# neural_network.net
KiCad netlist of a schematic drawn in EAGLE
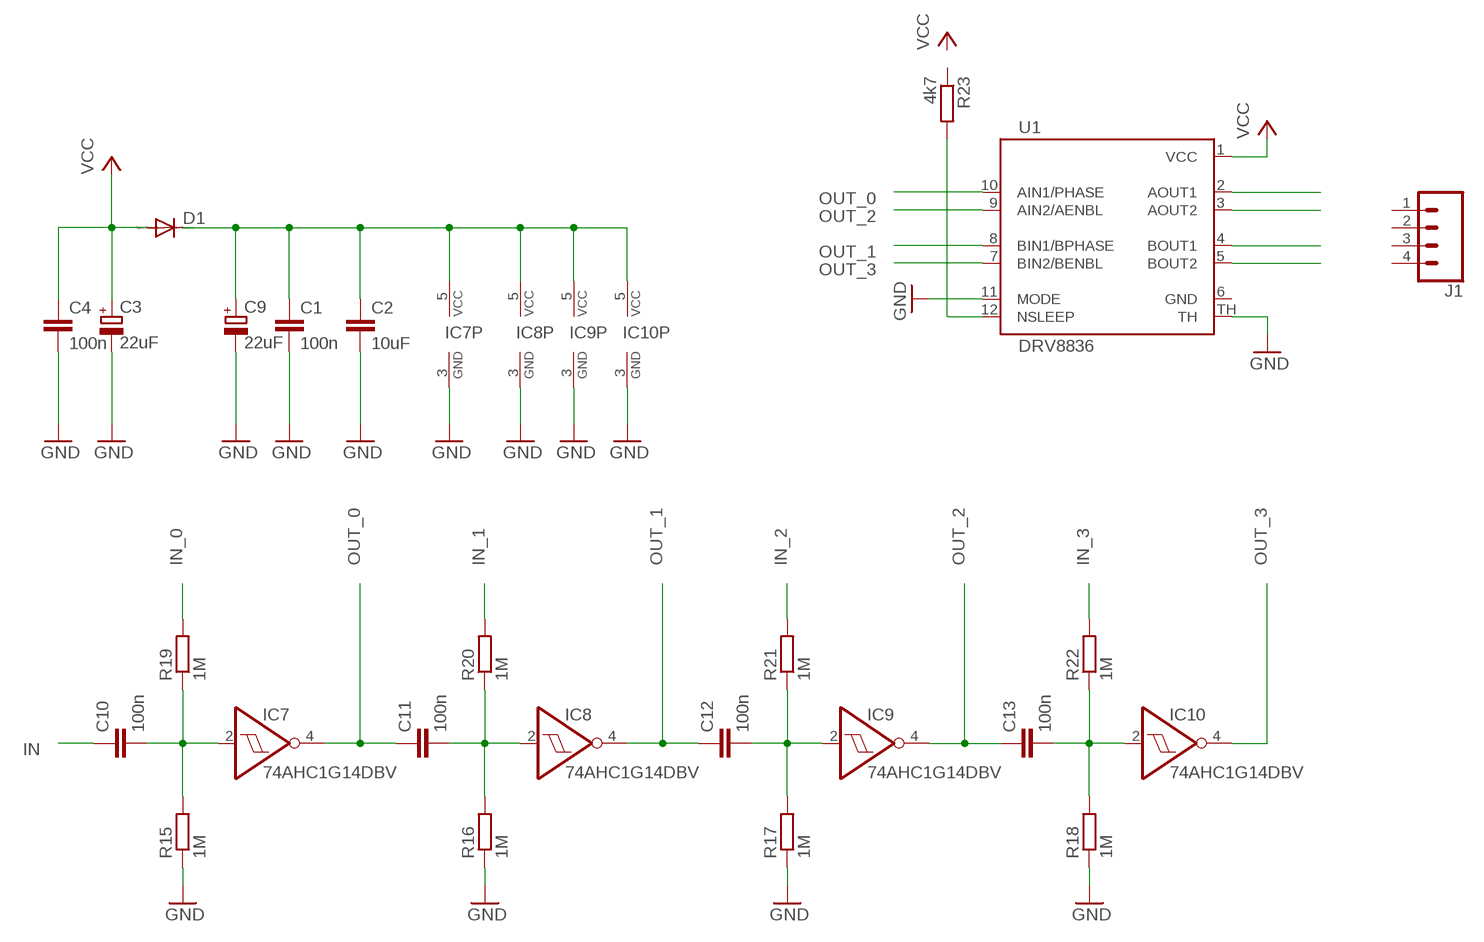
[diagram p0: schematic, sheet 1]

(export (version "E")
  (design (tool "Eeschema 10.0.6"))
  (components
    (comp (ref "C1")
      (value "100n")
      (footprint "eagle-import:C0805")
      (libsource (lib "eagle-import") (part "C-EUC0805"))
    )
    (comp (ref "C2")
      (value "10uF")
      (footprint "eagle-import:C0805")
      (libsource (lib "eagle-import") (part "C-EUC0805"))
    )
    (comp (ref "C3")
      (value "22uF")
      (footprint "eagle-import:153CLV-0605")
      (libsource (lib "eagle-import") (part "CPOL-EU153CLV-0605"))
    )
    (comp (ref "C4")
      (value "100n")
      (footprint "eagle-import:C0805")
      (libsource (lib "eagle-import") (part "C-EUC0805"))
    )
    (comp (ref "C9")
      (value "22uF")
      (footprint "eagle-import:153CLV-0605")
      (libsource (lib "eagle-import") (part "CPOL-EU153CLV-0605"))
    )
    (comp (ref "C10")
      (value "100n")
      (footprint "eagle-import:C0805")
      (libsource (lib "eagle-import") (part "C-EUC0805"))
    )
    (comp (ref "C11")
      (value "100n")
      (footprint "eagle-import:C0805")
      (libsource (lib "eagle-import") (part "C-EUC0805"))
    )
    (comp (ref "C12")
      (value "100n")
      (footprint "eagle-import:C0805")
      (libsource (lib "eagle-import") (part "C-EUC0805"))
    )
    (comp (ref "C13")
      (value "100n")
      (footprint "eagle-import:C0805")
      (libsource (lib "eagle-import") (part "C-EUC0805"))
    )
    (comp (ref "D1")
      (value "DIODE-DO214AA")
      (footprint "eagle-import:DO214AA")
      (libsource (lib "eagle-import") (part "DIODE-DO214AA"))
    )
    (comp (ref "IC7")
      (value "74AHC1G14DBV")
      (footprint "eagle-import:SOT23-5")
      (libsource (lib "eagle-import") (part "741G14DBVAHC"))
    )
    (comp (ref "IC8")
      (value "74AHC1G14DBV")
      (footprint "eagle-import:SOT23-5")
      (libsource (lib "eagle-import") (part "741G14DBVAHC"))
    )
    (comp (ref "IC9")
      (value "74AHC1G14DBV")
      (footprint "eagle-import:SOT23-5")
      (libsource (lib "eagle-import") (part "741G14DBVAHC"))
    )
    (comp (ref "IC10")
      (value "74AHC1G14DBV")
      (footprint "eagle-import:SOT23-5")
      (libsource (lib "eagle-import") (part "741G14DBVAHC"))
    )
    (comp (ref "J1")
      (value "CONN_04")
      (footprint "eagle-import:1X04")
      (libsource (lib "eagle-import") (part "CONN_04"))
    )
    (comp (ref "R15")
      (value "1M")
      (footprint "eagle-import:M0805")
      (libsource (lib "eagle-import") (part "R-EU_M0805"))
    )
    (comp (ref "R16")
      (value "1M")
      (footprint "eagle-import:M0805")
      (libsource (lib "eagle-import") (part "R-EU_M0805"))
    )
    (comp (ref "R17")
      (value "1M")
      (footprint "eagle-import:M0805")
      (libsource (lib "eagle-import") (part "R-EU_M0805"))
    )
    (comp (ref "R18")
      (value "1M")
      (footprint "eagle-import:M0805")
      (libsource (lib "eagle-import") (part "R-EU_M0805"))
    )
    (comp (ref "R19")
      (value "1M")
      (footprint "eagle-import:M0805")
      (libsource (lib "eagle-import") (part "R-EU_M0805"))
    )
    (comp (ref "R20")
      (value "1M")
      (footprint "eagle-import:M0805")
      (libsource (lib "eagle-import") (part "R-EU_M0805"))
    )
    (comp (ref "R21")
      (value "1M")
      (footprint "eagle-import:M0805")
      (libsource (lib "eagle-import") (part "R-EU_M0805"))
    )
    (comp (ref "R22")
      (value "1M")
      (footprint "eagle-import:M0805")
      (libsource (lib "eagle-import") (part "R-EU_M0805"))
    )
    (comp (ref "R23")
      (value "4k7")
      (footprint "eagle-import:M0805")
      (libsource (lib "eagle-import") (part "R-EU_M0805"))
    )
    (comp (ref "U1")
      (value "DRV8836")
      (footprint "eagle-import:12WSON")
      (libsource (lib "eagle-import") (part "DRV8836"))
    )
  )
  (nets
    (net (code "1") (name "/IN") (class "Default")
      (node (ref "C10") (pin "1") (pinfunction "1_1") (pintype "passive"))
    )
    (net (code "2") (name "/IN_0") (class "Default")
      (node (ref "R19") (pin "2") (pinfunction "2_2") (pintype "passive"))
    )
    (net (code "3") (name "/IN_1") (class "Default")
      (node (ref "R20") (pin "2") (pinfunction "2_2") (pintype "passive"))
    )
    (net (code "4") (name "/IN_2") (class "Default")
      (node (ref "R21") (pin "2") (pinfunction "2_2") (pintype "passive"))
    )
    (net (code "5") (name "/IN_3") (class "Default")
      (node (ref "R22") (pin "2") (pinfunction "2_2") (pintype "passive"))
    )
    (net (code "6") (name "/OUT_0") (class "Default")
      (node (ref "C11") (pin "1") (pinfunction "1_1") (pintype "passive"))
      (node (ref "IC7") (pin "4") (pinfunction "O_4") (pintype "output"))
      (node (ref "U1") (pin "10") (pinfunction "AIN1/PHASE_10") (pintype "bidirectional"))
    )
    (net (code "7") (name "/OUT_1") (class "Default")
      (node (ref "C12") (pin "1") (pinfunction "1_1") (pintype "passive"))
      (node (ref "IC8") (pin "4") (pinfunction "O_4") (pintype "output"))
      (node (ref "U1") (pin "8") (pinfunction "BIN1/BPHASE_8") (pintype "bidirectional"))
    )
    (net (code "8") (name "/OUT_2") (class "Default")
      (node (ref "C13") (pin "1") (pinfunction "1_1") (pintype "passive"))
      (node (ref "IC9") (pin "4") (pinfunction "O_4") (pintype "output"))
      (node (ref "U1") (pin "9") (pinfunction "AIN2/AENBL_9") (pintype "bidirectional"))
    )
    (net (code "9") (name "/OUT_3") (class "Default")
      (node (ref "IC10") (pin "4") (pinfunction "O_4") (pintype "output"))
      (node (ref "U1") (pin "7") (pinfunction "BIN2/BENBL_7") (pintype "bidirectional"))
    )
    (net (code "10") (name "GND") (class "Default")
      (node (ref "C1") (pin "2") (pinfunction "2_2") (pintype "passive"))
      (node (ref "C2") (pin "2") (pinfunction "2_2") (pintype "passive"))
      (node (ref "C3") (pin "-") (pinfunction "-_-") (pintype "passive"))
      (node (ref "C4") (pin "2") (pinfunction "2_2") (pintype "passive"))
      (node (ref "C9") (pin "-") (pinfunction "-_-") (pintype "passive"))
      (node (ref "IC10") (pin "3") (pinfunction "GND_3") (pintype "power_in"))
      (node (ref "IC7") (pin "3") (pinfunction "GND_3") (pintype "power_in"))
      (node (ref "IC8") (pin "3") (pinfunction "GND_3") (pintype "power_in"))
      (node (ref "IC9") (pin "3") (pinfunction "GND_3") (pintype "power_in"))
      (node (ref "R15") (pin "1") (pinfunction "1_1") (pintype "passive"))
      (node (ref "R16") (pin "1") (pinfunction "1_1") (pintype "passive"))
      (node (ref "R17") (pin "1") (pinfunction "1_1") (pintype "passive"))
      (node (ref "R18") (pin "1") (pinfunction "1_1") (pintype "passive"))
      (node (ref "U1") (pin "11") (pinfunction "MODE_11") (pintype "bidirectional"))
      (node (ref "U1") (pin "TH") (pinfunction "TH_TH") (pintype "bidirectional"))
    )
    (net (code "11") (name "Net-(IC7A-I)") (class "Default")
      (node (ref "C10") (pin "2") (pinfunction "2_2") (pintype "passive"))
      (node (ref "IC7") (pin "2") (pinfunction "I_2") (pintype "input"))
      (node (ref "R15") (pin "2") (pinfunction "2_2") (pintype "passive"))
      (node (ref "R19") (pin "1") (pinfunction "1_1") (pintype "passive"))
    )
    (net (code "12") (name "Net-(IC8A-I)") (class "Default")
      (node (ref "C11") (pin "2") (pinfunction "2_2") (pintype "passive"))
      (node (ref "IC8") (pin "2") (pinfunction "I_2") (pintype "input"))
      (node (ref "R16") (pin "2") (pinfunction "2_2") (pintype "passive"))
      (node (ref "R20") (pin "1") (pinfunction "1_1") (pintype "passive"))
    )
    (net (code "13") (name "Net-(IC9A-I)") (class "Default")
      (node (ref "C12") (pin "2") (pinfunction "2_2") (pintype "passive"))
      (node (ref "IC9") (pin "2") (pinfunction "I_2") (pintype "input"))
      (node (ref "R17") (pin "2") (pinfunction "2_2") (pintype "passive"))
      (node (ref "R21") (pin "1") (pinfunction "1_1") (pintype "passive"))
    )
    (net (code "14") (name "Net-(IC10A-I)") (class "Default")
      (node (ref "C13") (pin "2") (pinfunction "2_2") (pintype "passive"))
      (node (ref "IC10") (pin "2") (pinfunction "I_2") (pintype "input"))
      (node (ref "R18") (pin "2") (pinfunction "2_2") (pintype "passive"))
      (node (ref "R22") (pin "1") (pinfunction "1_1") (pintype "passive"))
    )
    (net (code "15") (name "Net-(IC10B-VCC)") (class "Default")
      (node (ref "C1") (pin "1") (pinfunction "1_1") (pintype "passive"))
      (node (ref "C2") (pin "1") (pinfunction "1_1") (pintype "passive"))
      (node (ref "C9") (pin "+") (pinfunction "+_+") (pintype "passive"))
      (node (ref "D1") (pin "C") (pinfunction "C_C") (pintype "passive"))
      (node (ref "IC10") (pin "5") (pinfunction "VCC_5") (pintype "power_in"))
      (node (ref "IC7") (pin "5") (pinfunction "VCC_5") (pintype "power_in"))
      (node (ref "IC8") (pin "5") (pinfunction "VCC_5") (pintype "power_in"))
      (node (ref "IC9") (pin "5") (pinfunction "VCC_5") (pintype "power_in"))
    )
    (net (code "16") (name "Net-(U1-NSLEEP)") (class "Default")
      (node (ref "R23") (pin "2") (pinfunction "2_2") (pintype "passive"))
      (node (ref "U1") (pin "12") (pinfunction "NSLEEP_12") (pintype "bidirectional"))
    )
    (net (code "17") (name "VCC") (class "Default")
      (node (ref "C3") (pin "+") (pinfunction "+_+") (pintype "passive"))
      (node (ref "C4") (pin "1") (pinfunction "1_1") (pintype "passive"))
      (node (ref "D1") (pin "A") (pinfunction "A_A") (pintype "passive"))
      (node (ref "U1") (pin "1") (pinfunction "VCC_1") (pintype "bidirectional"))
    )
    (net (code "18") (name "unconnected-(J1-Pad1)") (class "Default")
      (node (ref "J1") (pin "1") (pinfunction "1_1") (pintype "passive"))
    )
    (net (code "19") (name "unconnected-(J1-Pad2)") (class "Default")
      (node (ref "J1") (pin "2") (pinfunction "2_2") (pintype "passive"))
    )
    (net (code "20") (name "unconnected-(J1-Pad3)") (class "Default")
      (node (ref "J1") (pin "3") (pinfunction "3_3") (pintype "passive"))
    )
    (net (code "21") (name "unconnected-(J1-Pad4)") (class "Default")
      (node (ref "J1") (pin "4") (pinfunction "4_4") (pintype "passive"))
    )
    (net (code "22") (name "unconnected-(R23-Pad1)") (class "Default")
      (node (ref "R23") (pin "1") (pinfunction "1_1") (pintype "passive"))
    )
    (net (code "23") (name "unconnected-(U1-AOUT1-Pad2)") (class "Default")
      (node (ref "U1") (pin "2") (pinfunction "AOUT1_2") (pintype "bidirectional"))
    )
    (net (code "24") (name "unconnected-(U1-AOUT2-Pad3)") (class "Default")
      (node (ref "U1") (pin "3") (pinfunction "AOUT2_3") (pintype "bidirectional"))
    )
    (net (code "25") (name "unconnected-(U1-BOUT1-Pad4)") (class "Default")
      (node (ref "U1") (pin "4") (pinfunction "BOUT1_4") (pintype "bidirectional"))
    )
    (net (code "26") (name "unconnected-(U1-BOUT2-Pad5)") (class "Default")
      (node (ref "U1") (pin "5") (pinfunction "BOUT2_5") (pintype "bidirectional"))
    )
    (net (code "27") (name "unconnected-(U1-GND-Pad6)") (class "Default")
      (node (ref "U1") (pin "6") (pinfunction "GND_6") (pintype "bidirectional"))
    )
  )
)
